# SCH_HUB-USB_2025-02-06.net
KiCad netlist of a schematic drawn in EasyEDA
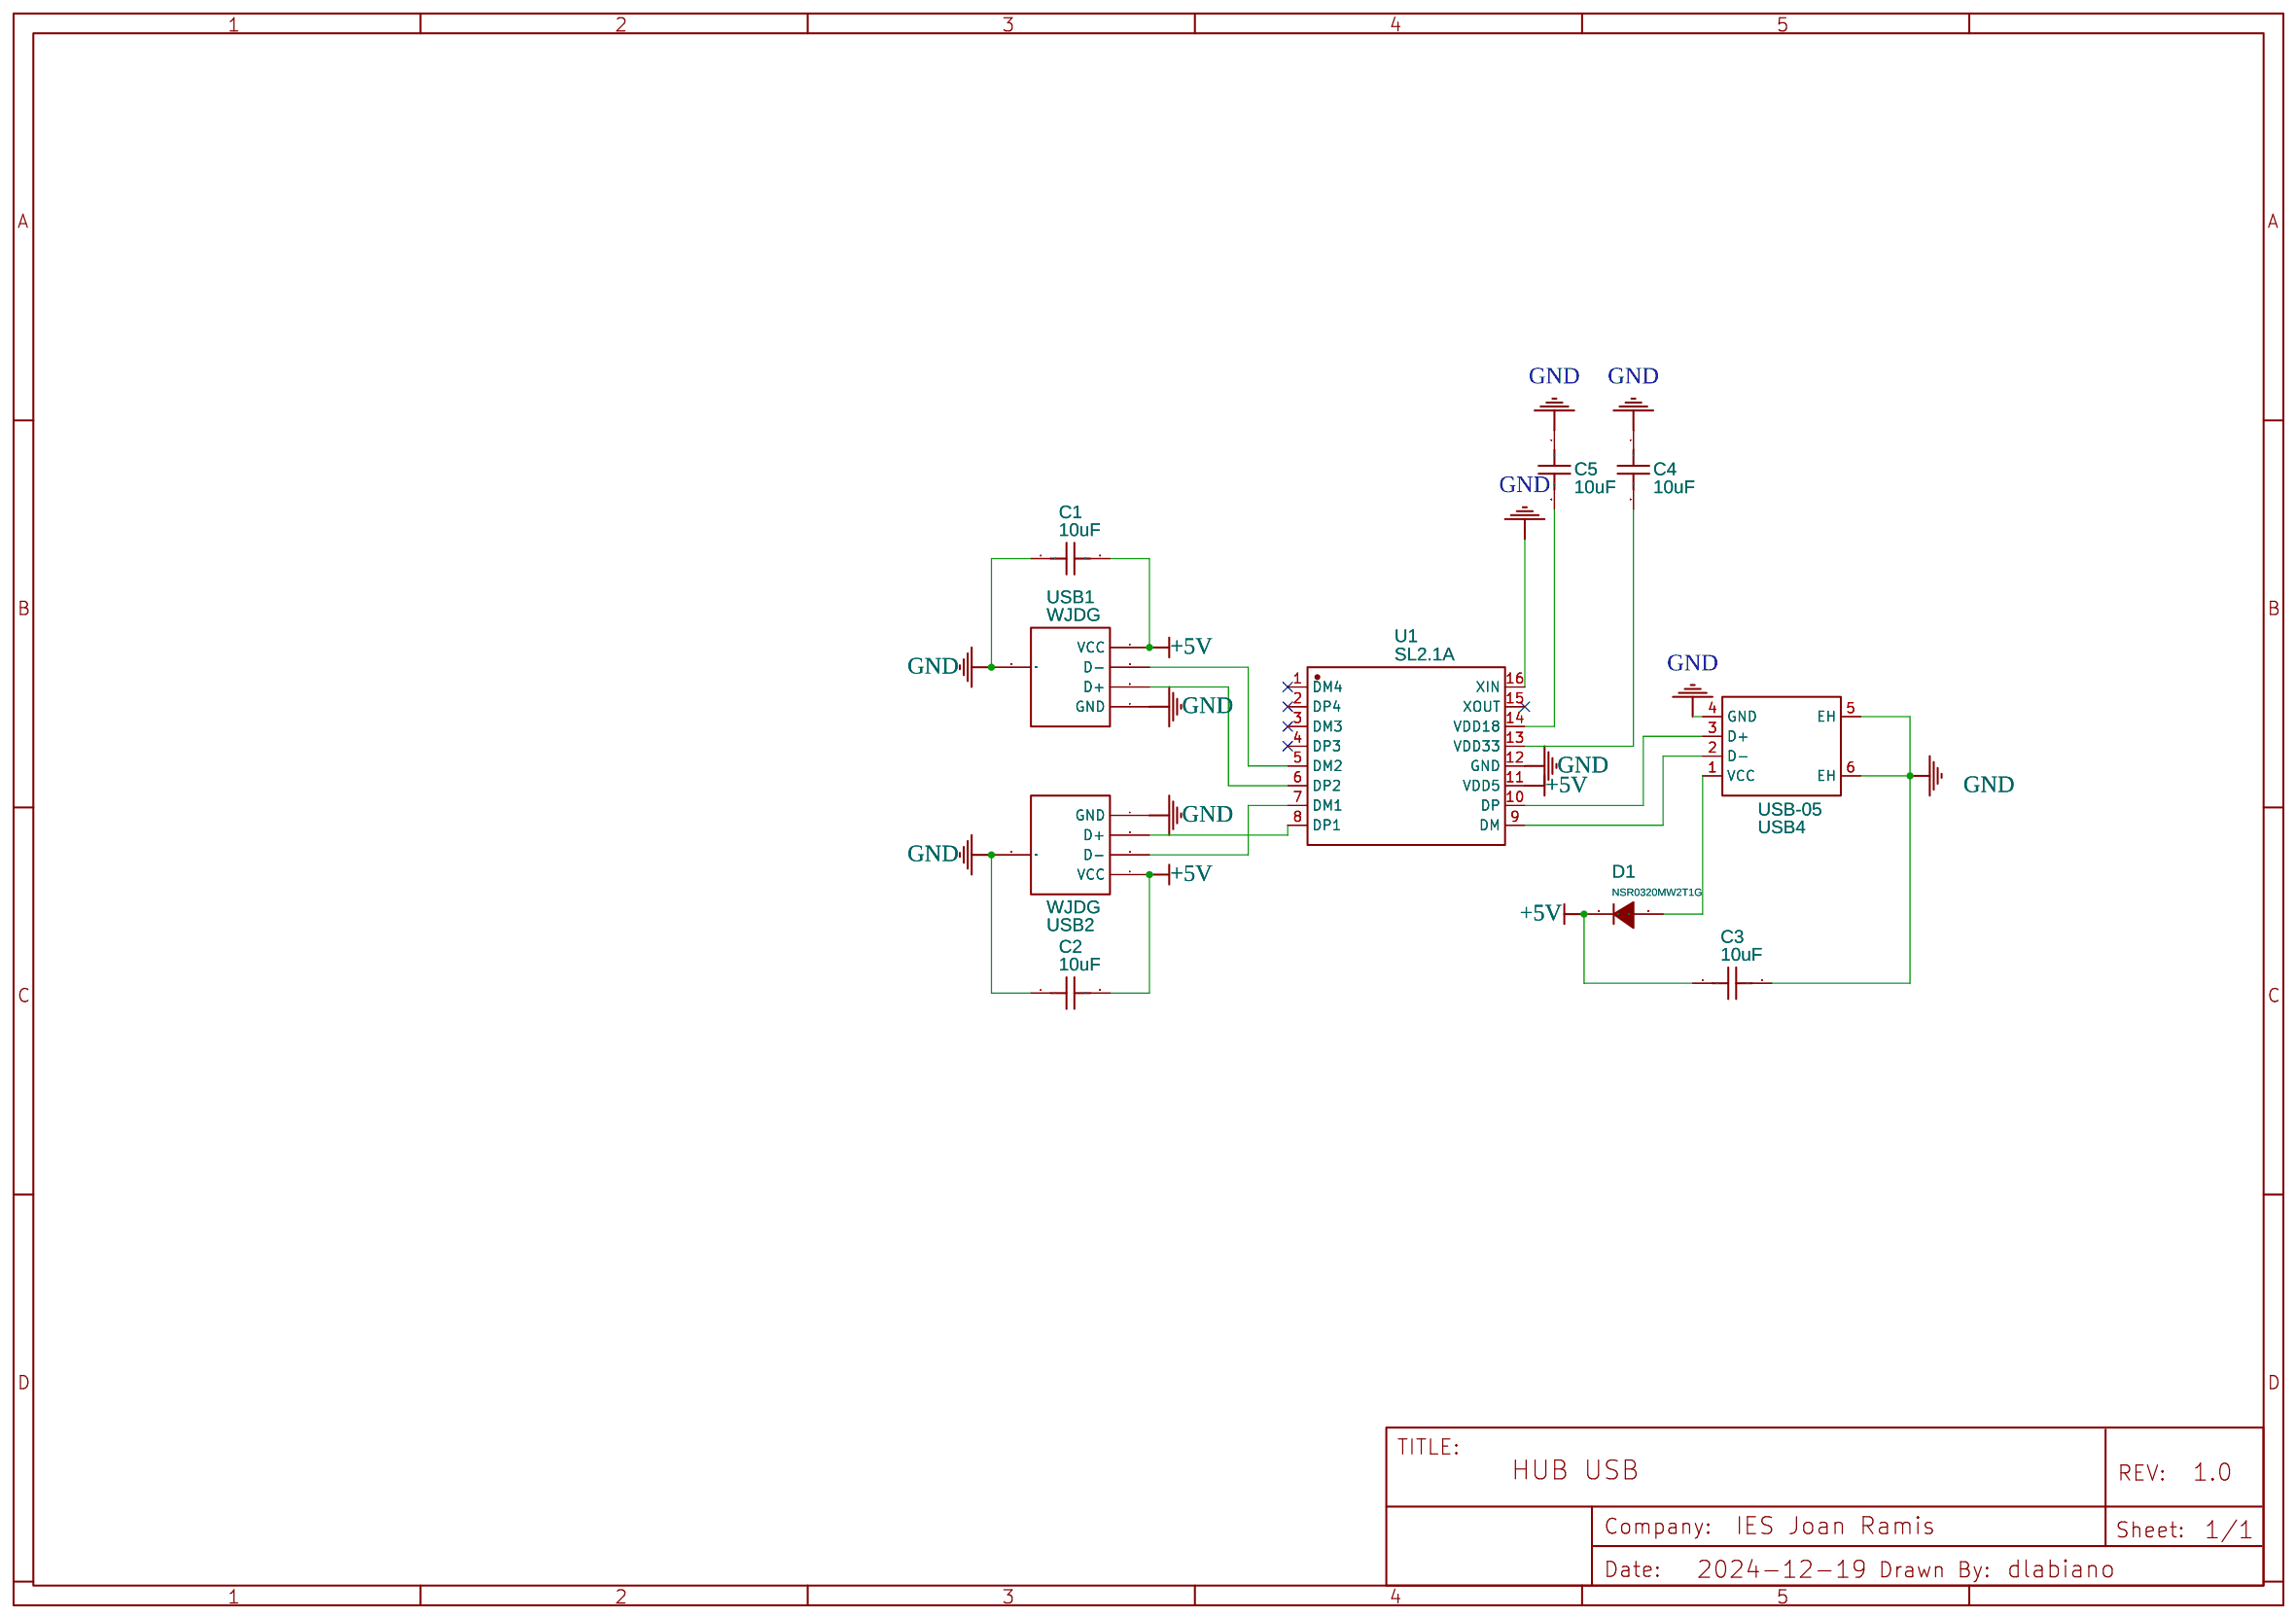
[diagram p0: schematic sheet]

(export (version "E")
  (design (tool "Eeschema 10.0.6"))
  (components
    (comp (ref "C1")
      (value "10uF")
      (fields
        (field (name "Manufacturer Part") "CL10A106KP8NNNC")
        (field (name "Manufacturer") "SAMSUNG(三星)")
      )
      (libsource (lib "") (part "CL10A106KP8NNNC"))
    )
    (comp (ref "C2")
      (value "10uF")
      (fields
        (field (name "Manufacturer Part") "CL10A106KP8NNNC")
        (field (name "Manufacturer") "SAMSUNG(三星)")
      )
      (libsource (lib "") (part "CL10A106KP8NNNC"))
    )
    (comp (ref "C3")
      (value "10uF")
      (fields
        (field (name "Manufacturer Part") "CL10A106KP8NNNC")
        (field (name "Manufacturer") "SAMSUNG(三星)")
      )
      (libsource (lib "") (part "CL10A106KP8NNNC"))
    )
    (comp (ref "C4")
      (value "10uF")
      (fields
        (field (name "Manufacturer Part") "CL10A106KP8NNNC")
        (field (name "Manufacturer") "SAMSUNG(三星)")
      )
      (libsource (lib "") (part "CL10A106KP8NNNC_1"))
    )
    (comp (ref "C5")
      (value "10uF")
      (fields
        (field (name "Manufacturer Part") "CL10A106KP8NNNC")
        (field (name "Manufacturer") "SAMSUNG(三星)")
      )
      (libsource (lib "") (part "CL10A106KP8NNNC_1"))
    )
    (comp (ref "D1")
      (value "NSR0320MW2T1G")
      (fields (field (name "Manufacturer") "onsemi(安森美)"))
      (libsource (lib "") (part "NSR0320MW2T1G"))
    )
    (comp (ref "U1")
      (value "SL2.1A")
      (fields (field (name "Manufacturer") "CoreChips(和芯润德)"))
      (libsource (lib "") (part "SL2.1A"))
    )
    (comp (ref "USB1")
      (value "WJDG")
      (fields (field (name "Manufacturer Part") "AF 90° WJDG") (field (name "Manufacturer") "SHOU HAN(首韩)"))
      (libsource (lib "") (part "AF 90° WJDG"))
    )
    (comp (ref "USB2")
      (value "WJDG")
      (fields (field (name "Manufacturer Part") "AF 90° WJDG") (field (name "Manufacturer") "SHOU HAN(首韩)"))
      (libsource (lib "") (part "AF 90° WJDG_1"))
    )
    (comp (ref "USB4")
      (value "USB-05")
      (fields (field (name "Manufacturer") "SOFNG(硕方)"))
      (libsource (lib "") (part "USB-05"))
    )
  )
  (nets
    (net (code "1") (name "+5V") (class "Default")
      (node (ref "C1") (pin "2") (pinfunction "2_2") (pintype "unspecified"))
      (node (ref "C2") (pin "2") (pinfunction "2_2") (pintype "unspecified"))
      (node (ref "C3") (pin "1") (pinfunction "1_1") (pintype "unspecified"))
      (node (ref "D1") (pin "1") (pinfunction "C_1") (pintype "unspecified"))
      (node (ref "U1") (pin "11") (pinfunction "VDD5_11") (pintype "unspecified"))
      (node (ref "USB1") (pin "1") (pinfunction "VCC_1") (pintype "input"))
      (node (ref "USB2") (pin "1") (pinfunction "VCC_1") (pintype "input"))
    )
    (net (code "2") (name "GND") (class "Default")
      (node (ref "C1") (pin "1") (pinfunction "1_1") (pintype "unspecified"))
      (node (ref "C2") (pin "1") (pinfunction "1_1") (pintype "unspecified"))
      (node (ref "C3") (pin "2") (pinfunction "2_2") (pintype "unspecified"))
      (node (ref "C4") (pin "1") (pinfunction "1_1") (pintype "unspecified"))
      (node (ref "C5") (pin "1") (pinfunction "1_1") (pintype "unspecified"))
      (node (ref "U1") (pin "12") (pinfunction "GND_12") (pintype "unspecified"))
      (node (ref "U1") (pin "16") (pinfunction "XIN_16") (pintype "unspecified"))
      (node (ref "USB1") (pin "4") (pinfunction "GND_4") (pintype "input"))
      (node (ref "USB1") (pin "5") (pinfunction "SHLD_5") (pintype "unspecified"))
      (node (ref "USB2") (pin "4") (pinfunction "GND_4") (pintype "input"))
      (node (ref "USB2") (pin "5") (pinfunction "SHLD_5") (pintype "unspecified"))
      (node (ref "USB4") (pin "4") (pinfunction "GND_4") (pintype "input"))
      (node (ref "USB4") (pin "5") (pinfunction "EH_5") (pintype "unspecified"))
      (node (ref "USB4") (pin "6") (pinfunction "EH_6") (pintype "unspecified"))
    )
    (net (code "3") (name "Net-(D1-A)") (class "Default")
      (node (ref "D1") (pin "2") (pinfunction "A_2") (pintype "unspecified"))
      (node (ref "USB4") (pin "1") (pinfunction "VCC_1") (pintype "input"))
    )
    (net (code "4") (name "Net-(U1-DM)") (class "Default")
      (node (ref "U1") (pin "9") (pinfunction "DM_9") (pintype "unspecified"))
      (node (ref "USB4") (pin "2") (pinfunction "D-_2") (pintype "input"))
    )
    (net (code "5") (name "Net-(U1-DM1)") (class "Default")
      (node (ref "U1") (pin "7") (pinfunction "DM1_7") (pintype "unspecified"))
      (node (ref "USB2") (pin "2") (pinfunction "D-_2") (pintype "input"))
    )
    (net (code "6") (name "Net-(U1-DM2)") (class "Default")
      (node (ref "U1") (pin "5") (pinfunction "DM2_5") (pintype "unspecified"))
      (node (ref "USB1") (pin "2") (pinfunction "D-_2") (pintype "input"))
    )
    (net (code "7") (name "Net-(U1-DP)") (class "Default")
      (node (ref "U1") (pin "10") (pinfunction "DP_10") (pintype "unspecified"))
      (node (ref "USB4") (pin "3") (pinfunction "D+_3") (pintype "input"))
    )
    (net (code "8") (name "Net-(U1-DP1)") (class "Default")
      (node (ref "U1") (pin "8") (pinfunction "DP1_8") (pintype "unspecified"))
      (node (ref "USB2") (pin "3") (pinfunction "D+_3") (pintype "input"))
    )
    (net (code "9") (name "Net-(U1-DP2)") (class "Default")
      (node (ref "U1") (pin "6") (pinfunction "DP2_6") (pintype "unspecified"))
      (node (ref "USB1") (pin "3") (pinfunction "D+_3") (pintype "input"))
    )
    (net (code "10") (name "Net-(U1-VDD18)") (class "Default")
      (node (ref "C5") (pin "2") (pinfunction "2_2") (pintype "unspecified"))
      (node (ref "U1") (pin "14") (pinfunction "VDD18_14") (pintype "unspecified"))
    )
    (net (code "11") (name "Net-(U1-VDD33)") (class "Default")
      (node (ref "C4") (pin "2") (pinfunction "2_2") (pintype "unspecified"))
      (node (ref "U1") (pin "13") (pinfunction "VDD33_13") (pintype "unspecified"))
    )
    (net (code "12") (name "unconnected-(U1-DM3-Pad3)") (class "Default")
      (node (ref "U1") (pin "3") (pinfunction "DM3_3") (pintype "unspecified+no_connect"))
    )
    (net (code "13") (name "unconnected-(U1-DM4-Pad1)") (class "Default")
      (node (ref "U1") (pin "1") (pinfunction "DM4_1") (pintype "unspecified+no_connect"))
    )
    (net (code "14") (name "unconnected-(U1-DP3-Pad4)") (class "Default")
      (node (ref "U1") (pin "4") (pinfunction "DP3_4") (pintype "unspecified+no_connect"))
    )
    (net (code "15") (name "unconnected-(U1-DP4-Pad2)") (class "Default")
      (node (ref "U1") (pin "2") (pinfunction "DP4_2") (pintype "unspecified+no_connect"))
    )
    (net (code "16") (name "unconnected-(U1-XOUT-Pad15)") (class "Default")
      (node (ref "U1") (pin "15") (pinfunction "XOUT_15") (pintype "unspecified+no_connect"))
    )
  )
)
